# Schematic_start_module_sumo_IR_V0_16_v1.net
KiCad netlist of a schematic drawn in EAGLE
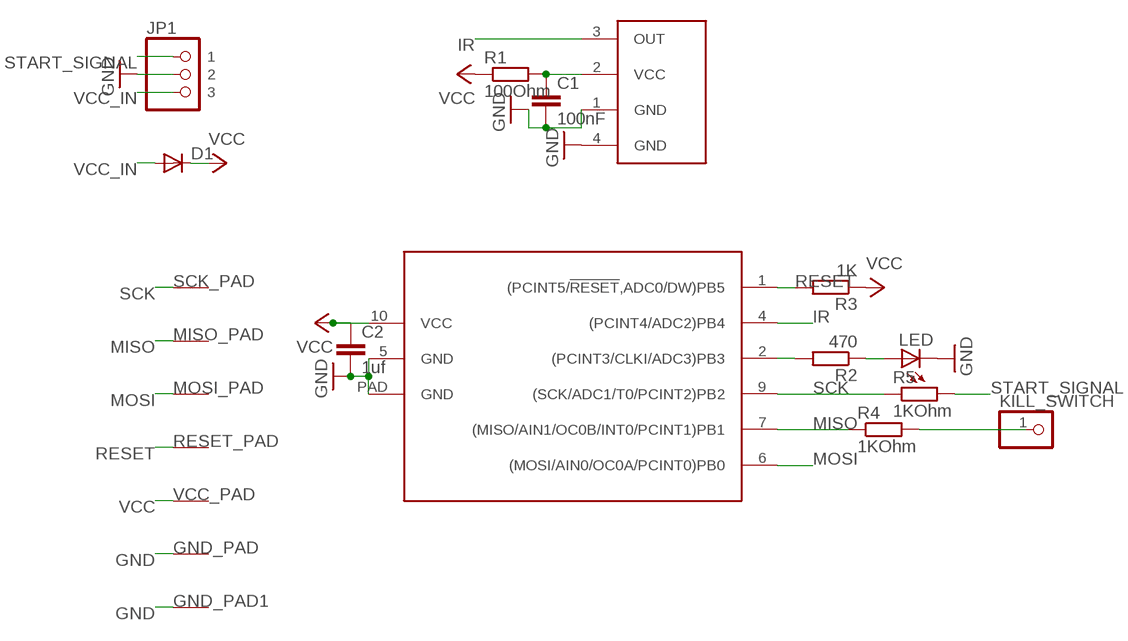
[diagram p0: schematic, sheet 1]

(export (version "E")
  (design (tool "Eeschema 10.0.6"))
  (components
    (comp (ref "C1")
      (value "100nF")
      (footprint "eagle-import:C0603")
      (libsource (lib "eagle-import") (part "C-EUC0603"))
    )
    (comp (ref "C2")
      (value "1uf")
      (footprint "eagle-import:C0603")
      (libsource (lib "eagle-import") (part "C-EUC0603"))
    )
    (comp (ref "D1")
      (value "DIODE-SOD523")
      (footprint "eagle-import:SOD523")
      (libsource (lib "eagle-import") (part "DIODE-SOD523"))
    )
    (comp (ref "GND_PAD")
      (value "PAD50X50")
      (footprint "eagle-import:PAD_50X50")
      (libsource (lib "eagle-import") (part "PAD50X50"))
    )
    (comp (ref "GND_PAD1")
      (value "PAD75X75")
      (footprint "eagle-import:PAD_75X75")
      (libsource (lib "eagle-import") (part "PAD75X75"))
    )
    (comp (ref "IR1")
      (value "TSOP77338TS")
      (footprint "eagle-import:TSOP77338")
      (libsource (lib "eagle-import") (part "TSOP77338TS"))
    )
    (comp (ref "JP1")
      (value "PINHD-1X3PIN")
      (footprint "eagle-import:1X3")
      (libsource (lib "eagle-import") (part "PINHD-1X3PIN"))
    )
    (comp (ref "KILL_SWITCH")
      (value "PINHD-1X1")
      (footprint "eagle-import:1X01")
      (libsource (lib "eagle-import") (part "PINHD-1X1"))
    )
    (comp (ref "LED")
      (value "LED0603")
      (footprint "eagle-import:0603_SMALL")
      (libsource (lib "eagle-import") (part "LED0603"))
    )
    (comp (ref "MISO_PAD")
      (value "PAD50X50")
      (footprint "eagle-import:PAD_50X50")
      (libsource (lib "eagle-import") (part "PAD50X50"))
    )
    (comp (ref "MOSI_PAD")
      (value "mosi")
      (footprint "eagle-import:PAD_75X75")
      (libsource (lib "eagle-import") (part "PAD75X75"))
    )
    (comp (ref "R1")
      (value "100Ohm")
      (footprint "eagle-import:R0603")
      (libsource (lib "eagle-import") (part "R-EU_R0603"))
    )
    (comp (ref "R2")
      (value "470")
      (footprint "eagle-import:R0603")
      (libsource (lib "eagle-import") (part "R-EU_R0603"))
    )
    (comp (ref "R3")
      (value "1K")
      (footprint "eagle-import:R0603")
      (libsource (lib "eagle-import") (part "R-EU_R0603"))
    )
    (comp (ref "R4")
      (value "1KOhm")
      (footprint "eagle-import:R0603")
      (libsource (lib "eagle-import") (part "R-EU_R0603"))
    )
    (comp (ref "R5")
      (value "1KOhm")
      (footprint "eagle-import:R0603")
      (libsource (lib "eagle-import") (part "R-EU_R0603"))
    )
    (comp (ref "RESET_PAD")
      (value "PAD50X50")
      (footprint "eagle-import:PAD_50X50")
      (libsource (lib "eagle-import") (part "PAD50X50"))
    )
    (comp (ref "SCK_PAD")
      (value "PAD50X50")
      (footprint "eagle-import:PAD_50X50")
      (libsource (lib "eagle-import") (part "PAD50X50"))
    )
    (comp (ref "UC")
      (value "ATTINY13A")
      (footprint "eagle-import:DFN10")
      (libsource (lib "eagle-import") (part "ATTINY13A"))
    )
    (comp (ref "VCC_PAD")
      (value "PAD50X50")
      (footprint "eagle-import:PAD_50X50")
      (libsource (lib "eagle-import") (part "PAD50X50"))
    )
  )
  (nets
    (net (code "1") (name "/IR") (class "Default")
      (node (ref "IR1") (pin "3") (pinfunction "OUT_3") (pintype "bidirectional"))
      (node (ref "UC") (pin "4") (pinfunction "(PCINT4/ADC2)PB4_4") (pintype "bidirectional"))
    )
    (net (code "2") (name "/MISO") (class "Default")
      (node (ref "MISO_PAD") (pin "P$1") (pinfunction "PAD_P$1") (pintype "power_in"))
      (node (ref "R4") (pin "1") (pinfunction "1_1") (pintype "passive"))
      (node (ref "UC") (pin "7") (pinfunction "(MISO/AIN1/OC0B/INT0/PCINT1)PB1_7") (pintype "bidirectional"))
    )
    (net (code "3") (name "/MOSI") (class "Default")
      (node (ref "MOSI_PAD") (pin "P$1") (pinfunction "PAD_P$1") (pintype "power_in"))
      (node (ref "UC") (pin "6") (pinfunction "(MOSI/AIN0/OC0A/PCINT0)PB0_6") (pintype "bidirectional"))
    )
    (net (code "4") (name "/RESET") (class "Default")
      (node (ref "R3") (pin "2") (pinfunction "2_2") (pintype "passive"))
      (node (ref "RESET_PAD") (pin "P$1") (pinfunction "PAD_P$1") (pintype "power_in"))
      (node (ref "UC") (pin "1") (pinfunction "(PCINT5/~{RESET,ADC0/DW})PB5_1") (pintype "bidirectional"))
    )
    (net (code "5") (name "/SCK") (class "Default")
      (node (ref "R5") (pin "1") (pinfunction "1_1") (pintype "passive"))
      (node (ref "SCK_PAD") (pin "P$1") (pinfunction "PAD_P$1") (pintype "power_in"))
      (node (ref "UC") (pin "9") (pinfunction "(SCK/ADC1/T0/PCINT2)PB2_9") (pintype "bidirectional"))
    )
    (net (code "6") (name "/START_SIGNAL") (class "Default")
      (node (ref "JP1") (pin "1") (pinfunction "1_1") (pintype "passive"))
      (node (ref "R5") (pin "2") (pinfunction "2_2") (pintype "passive"))
    )
    (net (code "7") (name "/VCC_IN") (class "Default")
      (node (ref "D1") (pin "A") (pinfunction "A_A") (pintype "passive"))
      (node (ref "JP1") (pin "3") (pinfunction "3_3") (pintype "passive"))
    )
    (net (code "8") (name "GND") (class "Default")
      (node (ref "C1") (pin "2") (pinfunction "2_2") (pintype "passive"))
      (node (ref "C2") (pin "2") (pinfunction "2_2") (pintype "passive"))
      (node (ref "GND_PAD") (pin "P$1") (pinfunction "PAD_P$1") (pintype "power_in"))
      (node (ref "GND_PAD1") (pin "P$1") (pinfunction "PAD_P$1") (pintype "power_in"))
      (node (ref "IR1") (pin "1") (pinfunction "GND_1") (pintype "bidirectional"))
      (node (ref "IR1") (pin "4") (pinfunction "GND_4") (pintype "bidirectional"))
      (node (ref "JP1") (pin "2") (pinfunction "2_2") (pintype "passive"))
      (node (ref "LED") (pin "2") (pinfunction "C_2") (pintype "passive"))
      (node (ref "UC") (pin "5") (pinfunction "GND_5") (pintype "bidirectional"))
      (node (ref "UC") (pin "PAD") (pinfunction "GND_PAD") (pintype "bidirectional"))
    )
    (net (code "9") (name "Net-(IR1-VCC)") (class "Default")
      (node (ref "C1") (pin "1") (pinfunction "1_1") (pintype "passive"))
      (node (ref "IR1") (pin "2") (pinfunction "VCC_2") (pintype "bidirectional"))
      (node (ref "R1") (pin "2") (pinfunction "2_2") (pintype "passive"))
    )
    (net (code "10") (name "Net-(KILL_SWITCH-Pad1)") (class "Default")
      (node (ref "KILL_SWITCH") (pin "1") (pinfunction "1_1") (pintype "passive"))
      (node (ref "R4") (pin "2") (pinfunction "2_2") (pintype "passive"))
    )
    (net (code "11") (name "Net-(LED-A)") (class "Default")
      (node (ref "LED") (pin "1") (pinfunction "A_1") (pintype "passive"))
      (node (ref "R2") (pin "1") (pinfunction "1_1") (pintype "passive"))
    )
    (net (code "12") (name "Net-(UC-(PCINT3{slash}CLKI{slash}ADC3)PB3)") (class "Default")
      (node (ref "R2") (pin "2") (pinfunction "2_2") (pintype "passive"))
      (node (ref "UC") (pin "2") (pinfunction "(PCINT3/CLKI/ADC3)PB3_2") (pintype "bidirectional"))
    )
    (net (code "13") (name "VCC") (class "Default")
      (node (ref "C2") (pin "1") (pinfunction "1_1") (pintype "passive"))
      (node (ref "D1") (pin "C") (pinfunction "C_C") (pintype "passive"))
      (node (ref "R1") (pin "1") (pinfunction "1_1") (pintype "passive"))
      (node (ref "R3") (pin "1") (pinfunction "1_1") (pintype "passive"))
      (node (ref "UC") (pin "10") (pinfunction "VCC_10") (pintype "bidirectional"))
      (node (ref "VCC_PAD") (pin "P$1") (pinfunction "PAD_P$1") (pintype "power_in"))
    )
  )
)
